# SparkFun_Temperature_Sensor-STTS22H.net
KiCad netlist of a schematic drawn in EAGLE
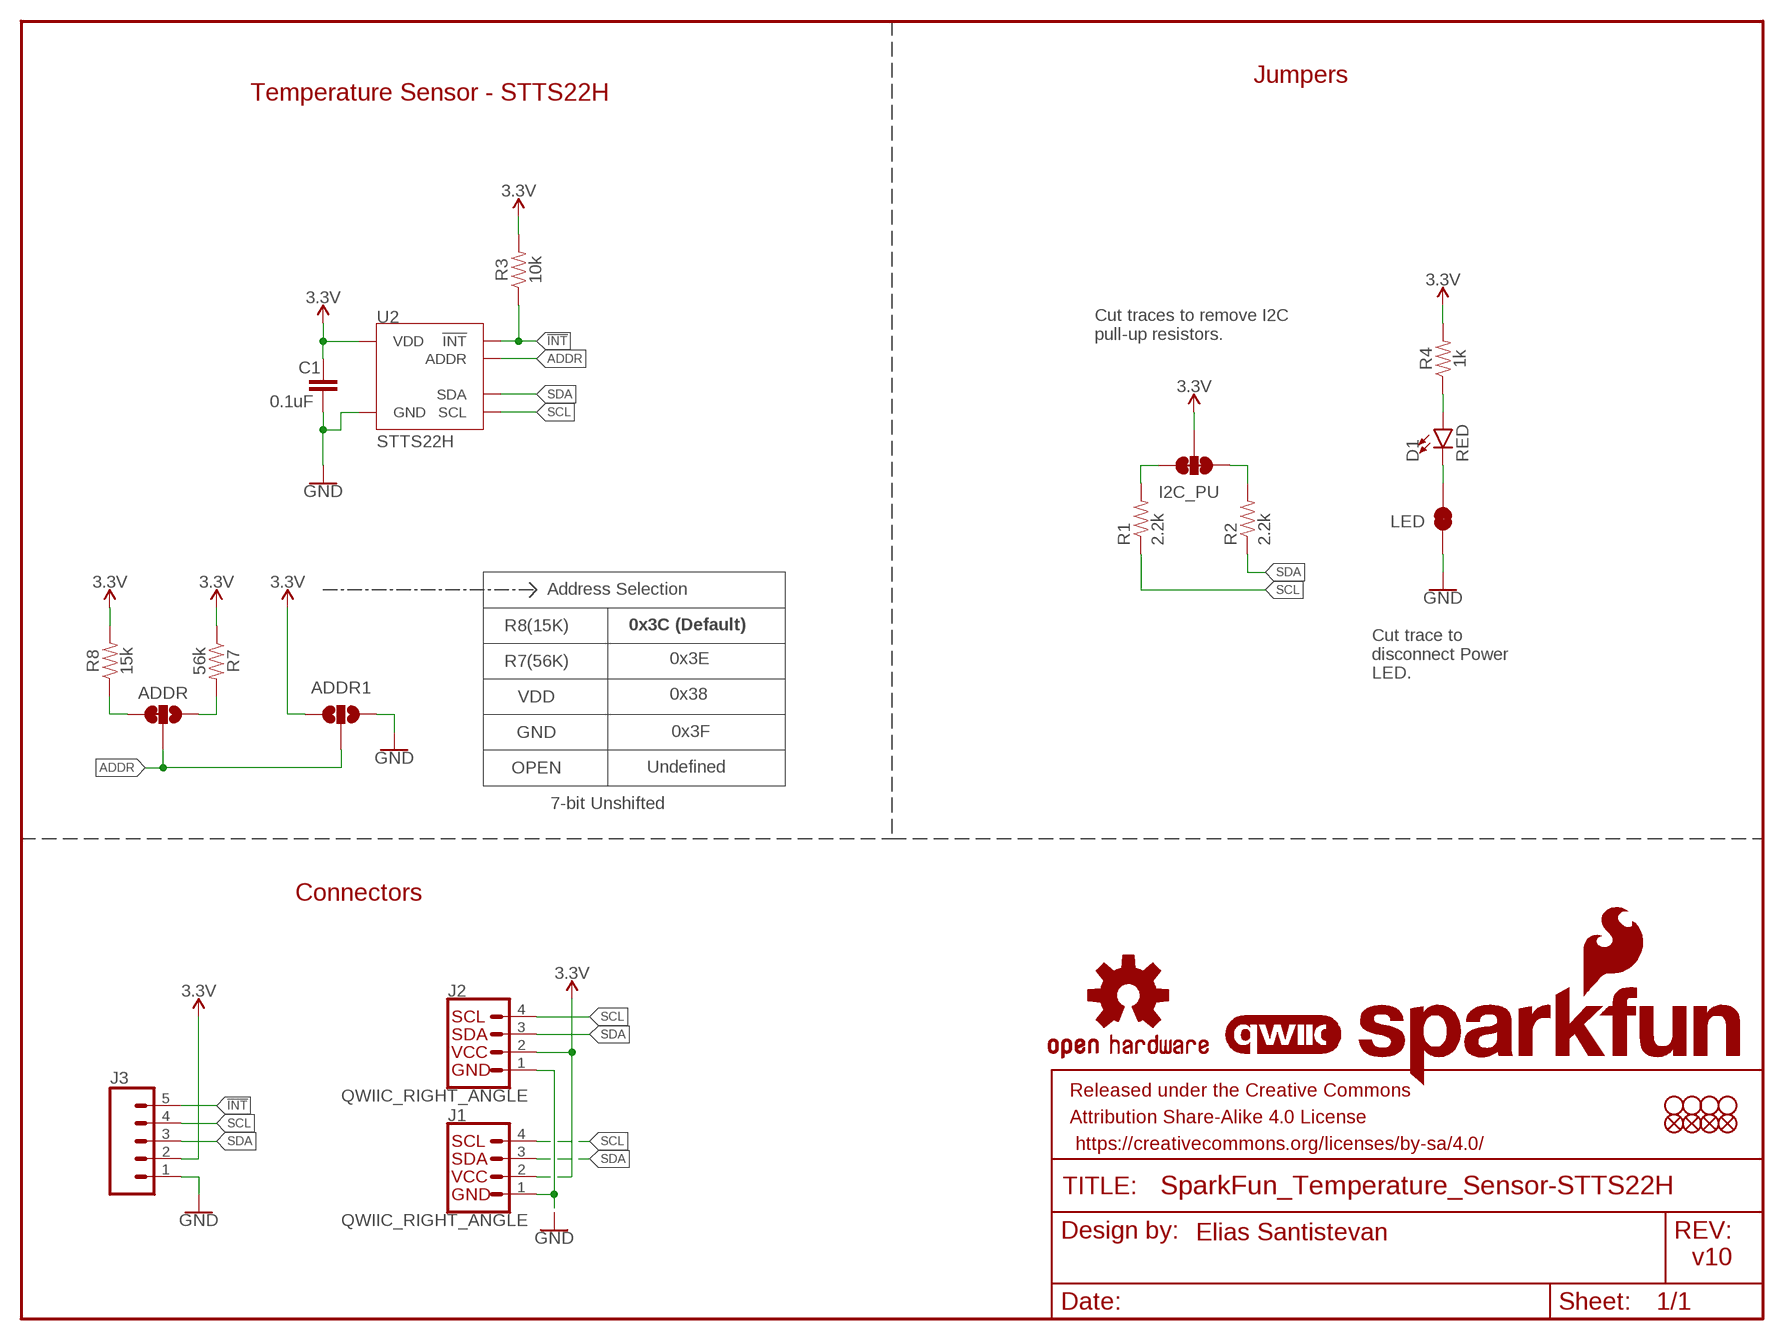
[diagram p0: schematic, sheet 1]

(export (version "E")
  (design (tool "Eeschema 10.0.6"))
  (components
    (comp (ref "ADDR")
      (value "JUMPER-SMT_3_1-NC_TRACE_SILK")
      (footprint "eagle-import:SMT-JUMPER_3_1-NC_TRACE_SILK")
      (libsource (lib "eagle-import") (part "JUMPER-SMT_3_1-NC_TRACE_SILK"))
    )
    (comp (ref "ADDR1")
      (value "JUMPER-SMT_3_NO_SILK")
      (footprint "eagle-import:SMT-JUMPER_3_NO_SILK")
      (libsource (lib "eagle-import") (part "JUMPER-SMT_3_NO_SILK"))
    )
    (comp (ref "C1")
      (value "0.1uF")
      (footprint "eagle-import:0603")
      (libsource (lib "eagle-import") (part "0.1UF-0603-25V-(+80/-20%)"))
    )
    (comp (ref "D1")
      (value "RED")
      (footprint "eagle-import:LED-0603")
      (libsource (lib "eagle-import") (part "LED-RED0603"))
    )
    (comp (ref "FD1")
      (value "FIDUCIAL1X2")
      (footprint "eagle-import:FIDUCIAL-1X2")
      (libsource (lib "eagle-import") (part "FIDUCIAL1X2"))
    )
    (comp (ref "FD2")
      (value "FIDUCIAL1X2")
      (footprint "eagle-import:FIDUCIAL-1X2")
      (libsource (lib "eagle-import") (part "FIDUCIAL1X2"))
    )
    (comp (ref "FD3")
      (value "FIDUCIAL1X2")
      (footprint "eagle-import:FIDUCIAL-1X2")
      (libsource (lib "eagle-import") (part "FIDUCIAL1X2"))
    )
    (comp (ref "FD4")
      (value "FIDUCIAL1X2")
      (footprint "eagle-import:FIDUCIAL-1X2")
      (libsource (lib "eagle-import") (part "FIDUCIAL1X2"))
    )
    (comp (ref "FRAME1")
      (value "FRAME-LETTER")
      (footprint "eagle-import:CREATIVE_COMMONS")
      (fields (field (name "DESIGNER") "Elias Santistevan"))
      (libsource (lib "eagle-import") (part "FRAME-LETTER"))
    )
    (comp (ref "I2C_PU")
      (value "S_MODE")
      (footprint "eagle-import:SMT-JUMPER_3_2-NC_TRACE_SILK")
      (libsource (lib "eagle-import") (part "JUMPER-SMT_3_2-NC_TRACE_SILK"))
    )
    (comp (ref "J1")
      (value "QWIIC_RIGHT_ANGLE")
      (footprint "eagle-import:JST04_1MM_RA")
      (libsource (lib "eagle-import") (part "QWIIC_CONNECTORJS-1MM"))
    )
    (comp (ref "J2")
      (value "QWIIC_RIGHT_ANGLE")
      (footprint "eagle-import:JST04_1MM_RA")
      (libsource (lib "eagle-import") (part "QWIIC_CONNECTORJS-1MM"))
    )
    (comp (ref "J3")
      (value "CONN_05NO_SILK")
      (footprint "eagle-import:1X05_NO_SILK")
      (libsource (lib "eagle-import") (part "CONN_05NO_SILK"))
    )
    (comp (ref "LED")
      (value "JUMPER-SMT_2_NC_TRACE_SILK")
      (footprint "eagle-import:SMT-JUMPER_2_NC_TRACE_SILK")
      (libsource (lib "eagle-import") (part "JUMPER-SMT_2_NC_TRACE_SILK"))
    )
    (comp (ref "LOGO2")
      (value "OSHW-LOGOMINI")
      (footprint "eagle-import:OSHW-LOGO-MINI")
      (libsource (lib "eagle-import") (part "OSHW-LOGOMINI"))
    )
    (comp (ref "LOGO3")
      (value "SFE_LOGO_NAME_FLAME.1_INCH")
      (footprint "eagle-import:SFE_LOGO_NAME_FLAME_.1")
      (libsource (lib "eagle-import") (part "SFE_LOGO_NAME_FLAME.1_INCH"))
    )
    (comp (ref "LOGO4")
      (value "QWIIC_LOGO_4MM")
      (footprint "eagle-import:QWIIC_4MM")
      (libsource (lib "eagle-import") (part "QWIIC_LOGO_4MM"))
    )
    (comp (ref "R1")
      (value "2.2k")
      (footprint "eagle-import:0603")
      (libsource (lib "eagle-import") (part "2.2KOHM-0603-1/10W-1%"))
    )
    (comp (ref "R2")
      (value "2.2k")
      (footprint "eagle-import:0603")
      (libsource (lib "eagle-import") (part "2.2KOHM-0603-1/10W-1%"))
    )
    (comp (ref "R3")
      (value "10k")
      (footprint "eagle-import:0603")
      (libsource (lib "eagle-import") (part "10KOHM-0603-1/10W-1%"))
    )
    (comp (ref "R4")
      (value "1k")
      (footprint "eagle-import:0603")
      (libsource (lib "eagle-import") (part "1KOHM-0603-1/10W-1%"))
    )
    (comp (ref "R7")
      (value "56k")
      (footprint "eagle-import:0603")
      (libsource (lib "eagle-import") (part "56KOHM"))
    )
    (comp (ref "R8")
      (value "15k")
      (footprint "eagle-import:0603")
      (libsource (lib "eagle-import") (part "15KOHM-0603-1/10W-1%"))
    )
    (comp (ref "STANDOFF1")
      (value "STAND-OFFTIGHT")
      (footprint "eagle-import:STAND-OFF-TIGHT")
      (libsource (lib "eagle-import") (part "STAND-OFFTIGHT"))
    )
    (comp (ref "STANDOFF2")
      (value "STAND-OFFTIGHT")
      (footprint "eagle-import:STAND-OFF-TIGHT")
      (libsource (lib "eagle-import") (part "STAND-OFFTIGHT"))
    )
    (comp (ref "STANDOFF3")
      (value "STAND-OFFTIGHT")
      (footprint "eagle-import:STAND-OFF-TIGHT")
      (libsource (lib "eagle-import") (part "STAND-OFFTIGHT"))
    )
    (comp (ref "STANDOFF5")
      (value "STAND-OFFTIGHT")
      (footprint "eagle-import:STAND-OFF-TIGHT")
      (libsource (lib "eagle-import") (part "STAND-OFFTIGHT"))
    )
    (comp (ref "U2")
      (value "STTS22H")
      (footprint "eagle-import:UDFN-6L")
      (libsource (lib "eagle-import") (part "STTS22H"))
    )
  )
  (nets
    (net (code "1") (name "/~{INT}") (class "Default")
      (node (ref "J3") (pin "5") (pinfunction "5_5") (pintype "passive"))
      (node (ref "R3") (pin "1") (pinfunction "1_1") (pintype "passive"))
      (node (ref "U2") (pin "P2") (pinfunction "~{INT}_P2") (pintype "bidirectional"))
    )
    (net (code "2") (name "3.3V") (class "Default")
      (node (ref "ADDR1") (pin "3") (pinfunction "3_3") (pintype "passive"))
      (node (ref "C1") (pin "1") (pinfunction "1_1") (pintype "passive"))
      (node (ref "I2C_PU") (pin "2") (pinfunction "2_2") (pintype "passive"))
      (node (ref "J1") (pin "2") (pinfunction "2_2") (pintype "power_in"))
      (node (ref "J2") (pin "2") (pinfunction "2_2") (pintype "power_in"))
      (node (ref "J3") (pin "2") (pinfunction "2_2") (pintype "passive"))
      (node (ref "R3") (pin "2") (pinfunction "2_2") (pintype "passive"))
      (node (ref "R4") (pin "2") (pinfunction "2_2") (pintype "passive"))
      (node (ref "R7") (pin "1") (pinfunction "1_1") (pintype "passive"))
      (node (ref "R8") (pin "2") (pinfunction "2_2") (pintype "passive"))
      (node (ref "U2") (pin "P3") (pinfunction "VDD_P3") (pintype "power_in"))
    )
    (net (code "3") (name "ADDR") (class "Default")
      (node (ref "ADDR") (pin "2") (pinfunction "2_2") (pintype "passive"))
      (node (ref "ADDR1") (pin "2") (pinfunction "2_2") (pintype "passive"))
      (node (ref "U2") (pin "P4") (pinfunction "ADDR_P4") (pintype "bidirectional"))
    )
    (net (code "4") (name "GND") (class "Default")
      (node (ref "ADDR1") (pin "1") (pinfunction "1_1") (pintype "passive"))
      (node (ref "C1") (pin "2") (pinfunction "2_2") (pintype "passive"))
      (node (ref "J1") (pin "1") (pinfunction "1_1") (pintype "power_in"))
      (node (ref "J2") (pin "1") (pinfunction "1_1") (pintype "power_in"))
      (node (ref "J3") (pin "1") (pinfunction "1_1") (pintype "passive"))
      (node (ref "LED") (pin "1") (pinfunction "1_1") (pintype "passive"))
      (node (ref "U2") (pin "P5") (pinfunction "GND_P5") (pintype "power_in"))
      (node (ref "U2") (pin "P7") (pinfunction "GND_P7") (pintype "power_in"))
    )
    (net (code "5") (name "Net-(ADDR-Pad1)") (class "Default")
      (node (ref "ADDR") (pin "1") (pinfunction "1_1") (pintype "passive"))
      (node (ref "R7") (pin "2") (pinfunction "2_2") (pintype "passive"))
    )
    (net (code "6") (name "Net-(ADDR-Pad3)") (class "Default")
      (node (ref "ADDR") (pin "3") (pinfunction "3_3") (pintype "passive"))
      (node (ref "R8") (pin "1") (pinfunction "1_1") (pintype "passive"))
    )
    (net (code "7") (name "Net-(D1-PadA)") (class "Default")
      (node (ref "D1") (pin "A") (pinfunction "A_A") (pintype "passive"))
      (node (ref "R4") (pin "1") (pinfunction "1_1") (pintype "passive"))
    )
    (net (code "8") (name "Net-(D1-PadC)") (class "Default")
      (node (ref "D1") (pin "C") (pinfunction "C_C") (pintype "passive"))
      (node (ref "LED") (pin "2") (pinfunction "2_2") (pintype "passive"))
    )
    (net (code "9") (name "Net-(I2C_PU-Pad1)") (class "Default")
      (node (ref "I2C_PU") (pin "1") (pinfunction "1_1") (pintype "passive"))
      (node (ref "R1") (pin "2") (pinfunction "2_2") (pintype "passive"))
    )
    (net (code "10") (name "Net-(I2C_PU-Pad3)") (class "Default")
      (node (ref "I2C_PU") (pin "3") (pinfunction "3_3") (pintype "passive"))
      (node (ref "R2") (pin "2") (pinfunction "2_2") (pintype "passive"))
    )
    (net (code "11") (name "SCL") (class "Default")
      (node (ref "J1") (pin "4") (pinfunction "4_4") (pintype "passive"))
      (node (ref "J2") (pin "4") (pinfunction "4_4") (pintype "passive"))
      (node (ref "J3") (pin "4") (pinfunction "4_4") (pintype "passive"))
      (node (ref "R1") (pin "1") (pinfunction "1_1") (pintype "passive"))
      (node (ref "U2") (pin "P1") (pinfunction "SCL_P1") (pintype "bidirectional"))
    )
    (net (code "12") (name "SDA") (class "Default")
      (node (ref "J1") (pin "3") (pinfunction "3_3") (pintype "passive"))
      (node (ref "J2") (pin "3") (pinfunction "3_3") (pintype "passive"))
      (node (ref "J3") (pin "3") (pinfunction "3_3") (pintype "passive"))
      (node (ref "R2") (pin "1") (pinfunction "1_1") (pintype "passive"))
      (node (ref "U2") (pin "P6") (pinfunction "SDA_P6") (pintype "bidirectional"))
    )
  )
)
